# BQ76940.net
KiCad netlist of a schematic drawn in Altium Designer
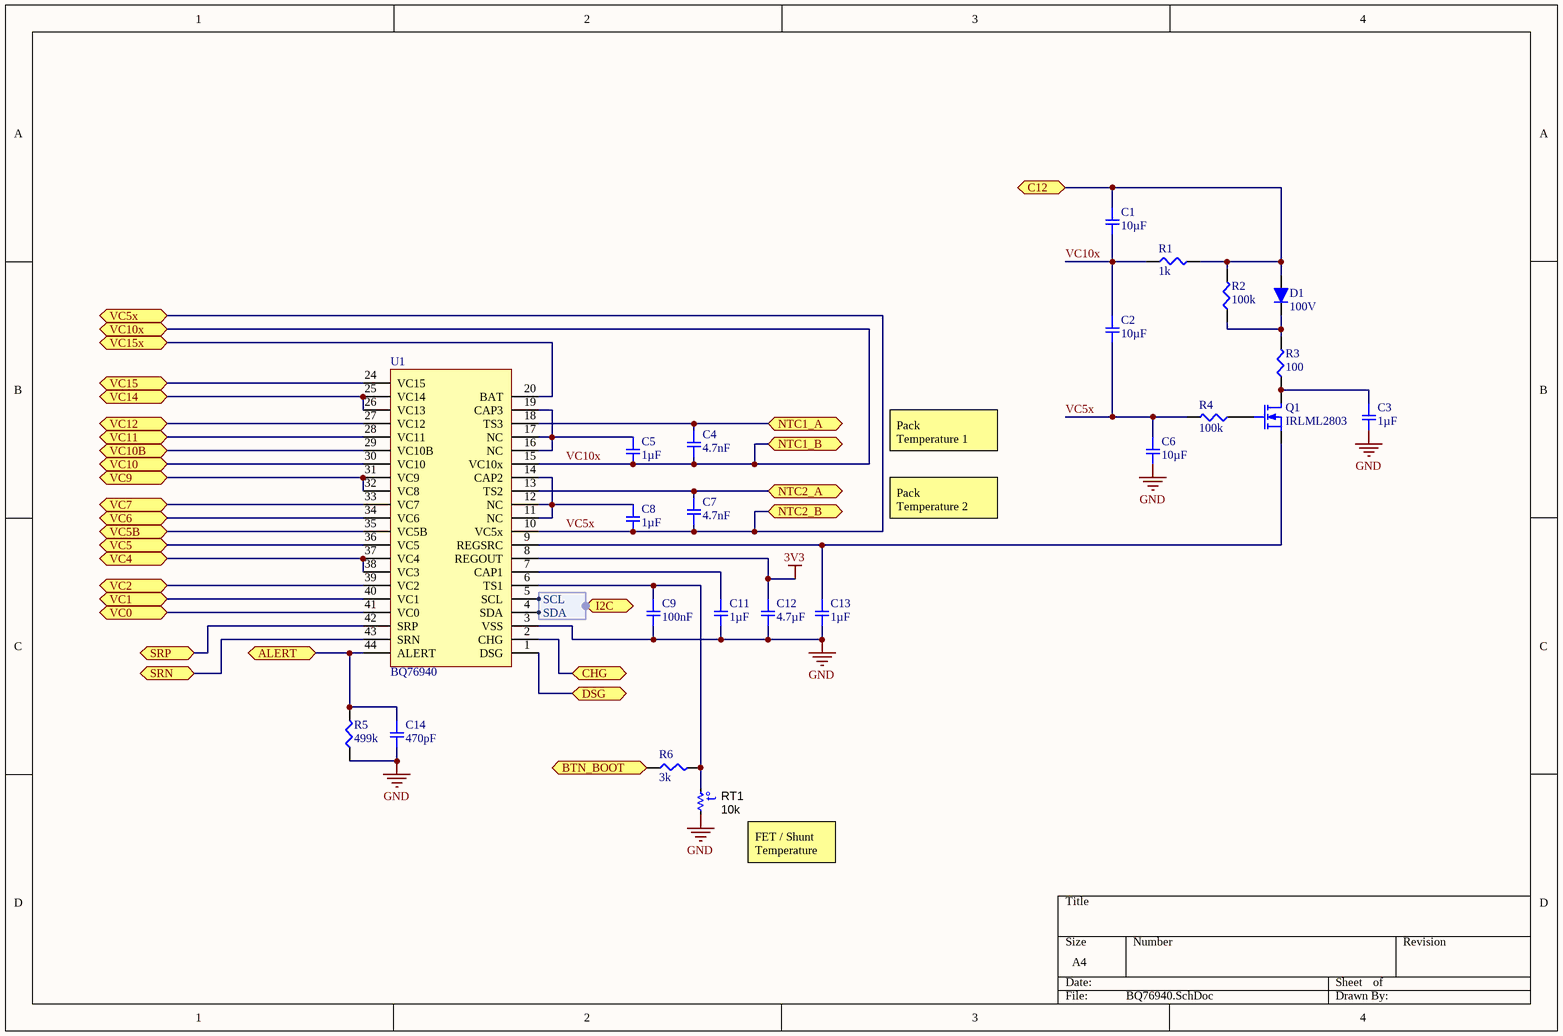
[diagram p0: BQ76940.SchDoc]

(export (version "E")
  (design (tool "Eeschema 10.0.6"))
  (components
    (comp (ref "C1")
      (value "10µF")
      (footprint "SMD-0603C")
      (description "CAP CER 10UF 6.3V X5R 0603")
      (fields
        (field (name "DIGI-KEY PART NUMBER") "490-10467-1-ND")
        (field (name "PART NUMBER") "GRM185R60J106ME15D")
      )
      (libsource (lib "capacitor_murata_0603") (part "GRM185R60J106ME15D"))
    )
    (comp (ref "C2")
      (value "10µF")
      (footprint "SMD-0603C")
      (description "CAP CER 10UF 6.3V X5R 0603")
      (fields
        (field (name "DIGI-KEY PART NUMBER") "490-10467-1-ND")
        (field (name "PART NUMBER") "GRM185R60J106ME15D")
      )
      (libsource (lib "capacitor_murata_0603") (part "GRM185R60J106ME15D"))
    )
    (comp (ref "C3")
      (value "1µF")
      (footprint "SMD-0603C")
      (description "CAP CER 1UF 16V X7R 0603")
      (fields
        (field (name "DIGI-KEY PART NUMBER") "490-5241-1-ND")
        (field (name "PART NUMBER") "GCM188R71C105KA64D")
      )
      (libsource (lib "capacitor_murata_0603") (part "GCM188R71C105KA64D"))
    )
    (comp (ref "C4")
      (value "4.7nF")
      (footprint "SMD-0603C")
      (description "CAP CER 4700PF 50V X7R 0603")
      (fields
        (field (name "DIGI-KEY PART NUMBER") "490-10897-1-ND")
        (field (name "PART NUMBER") "GRJ188R71H472KE11D")
      )
      (libsource (lib "capacitor_murata_0603") (part "GRJ188R71H472KE11D"))
    )
    (comp (ref "C5")
      (value "1µF")
      (footprint "SMD-0603C")
      (description "CAP CER 1UF 16V X7R 0603")
      (fields
        (field (name "DIGI-KEY PART NUMBER") "490-5241-1-ND")
        (field (name "PART NUMBER") "GCM188R71C105KA64D")
      )
      (libsource (lib "capacitor_murata_0603") (part "GCM188R71C105KA64D"))
    )
    (comp (ref "C6")
      (value "10µF")
      (footprint "SMD-0603C")
      (description "CAP CER 10UF 6.3V X5R 0603")
      (fields
        (field (name "DIGI-KEY PART NUMBER") "490-10467-1-ND")
        (field (name "PART NUMBER") "GRM185R60J106ME15D")
      )
      (libsource (lib "capacitor_murata_0603") (part "GRM185R60J106ME15D"))
    )
    (comp (ref "C7")
      (value "4.7nF")
      (footprint "SMD-0603C")
      (description "CAP CER 4700PF 50V X7R 0603")
      (fields
        (field (name "DIGI-KEY PART NUMBER") "490-10897-1-ND")
        (field (name "PART NUMBER") "GRJ188R71H472KE11D")
      )
      (libsource (lib "capacitor_murata_0603") (part "GRJ188R71H472KE11D"))
    )
    (comp (ref "C8")
      (value "1µF")
      (footprint "SMD-0603C")
      (description "CAP CER 1UF 16V X7R 0603")
      (fields
        (field (name "DIGI-KEY PART NUMBER") "490-5241-1-ND")
        (field (name "PART NUMBER") "GCM188R71C105KA64D")
      )
      (libsource (lib "capacitor_murata_0603") (part "GCM188R71C105KA64D"))
    )
    (comp (ref "C9")
      (value "100nF")
      (footprint "SMD-0603C")
      (description "CAP CER 0.1UF 16V X7R 0603")
      (fields
        (field (name "DIGI-KEY PART NUMBER") "490-5796-1-ND")
        (field (name "PART NUMBER") "GCJ188R71C104KA01D")
      )
      (libsource (lib "capacitor_murata_0603") (part "GCJ188R71C104KA01D"))
    )
    (comp (ref "C11")
      (value "1µF")
      (footprint "SMD-0603C")
      (description "CAP CER 1UF 16V X7R 0603")
      (fields
        (field (name "DIGI-KEY PART NUMBER") "490-5241-1-ND")
        (field (name "PART NUMBER") "GCM188R71C105KA64D")
      )
      (libsource (lib "capacitor_murata_0603") (part "GCM188R71C105KA64D"))
    )
    (comp (ref "C12")
      (value "4.7µF")
      (footprint "SMD-0603C")
      (description "CAP CER 4.7UF 6.3V X7S 0603")
      (fields
        (field (name "DIGI-KEY PART NUMBER") "490-10884-1-ND")
        (field (name "PART NUMBER") "GRJ188C70J475KE11D")
      )
      (libsource (lib "capacitor_murata_0603") (part "GRJ188C70J475KE11D"))
    )
    (comp (ref "C13")
      (value "1µF")
      (footprint "SMD-0603C")
      (description "CAP CER 1UF 16V X7R 0603")
      (fields
        (field (name "DIGI-KEY PART NUMBER") "490-5241-1-ND")
        (field (name "PART NUMBER") "GCM188R71C105KA64D")
      )
      (libsource (lib "capacitor_murata_0603") (part "GCM188R71C105KA64D"))
    )
    (comp (ref "C14")
      (value "470pF")
      (footprint "SMD-0603C")
      (description "CAP CER 470PF 50V NP0 0603")
      (fields
        (field (name "DIGI-KEY PART NUMBER") "490-4965-1-ND")
        (field (name "PART NUMBER") "GCM1885C1H471JA16D")
      )
      (libsource (lib "capacitor_murata_0603") (part "GCM1885C1H471JA16D"))
    )
    (comp (ref "D1")
      (value "100V")
      (footprint "SOD-323")
      (description "Diode")
      (libsource (lib "Components") (part "DIODE"))
    )
    (comp (ref "Q1")
      (value "IRLML2803")
      (footprint "SOT23-3")
      (description "N-Channel MOSFET")
      (fields (field (name "PUBLISHER") "Altium Limited"))
      (libsource (lib "Components") (part "MOSFET-N"))
    )
    (comp (ref "R1")
      (value "1k")
      (footprint "SMD-0603-RES")
      (description "RES SMD 1K OHM 1% 1/10W 0603")
      (fields
        (field (name "PART NUMBER") "ERJ-3EKF1001V")
        (field (name "DIGI-KEY PART NUMBER") "P1.00KHCT-ND")
      )
      (libsource (lib "Panasonic_ERJ_0603") (part "ERJ-3EKF1001V"))
    )
    (comp (ref "R2")
      (value "100k")
      (footprint "SMD-0603-RES")
      (description "RES SMD 100K OHM 1% 1/10W 0603")
      (fields
        (field (name "PART NUMBER") "ERJ-3EKF1003V")
        (field (name "DIGI-KEY PART NUMBER") "P100KHCT-ND")
      )
      (libsource (lib "Panasonic_ERJ_0603") (part "ERJ-3EKF1003V"))
    )
    (comp (ref "R3")
      (value "100")
      (footprint "SMD-0603-RES")
      (description "RES SMD 100 OHM 1% 1/10W 0603")
      (fields (field (name "PART NUMBER") "ERJ-3EKF1000V") (field (name "DIGI-KEY PART NUMBER") "P100HCT-ND"))
      (libsource (lib "Panasonic_ERJ_0603") (part "ERJ-3EKF1000V"))
    )
    (comp (ref "R4")
      (value "100k")
      (footprint "SMD-0603-RES")
      (description "RES SMD 100K OHM 1% 1/10W 0603")
      (fields
        (field (name "PART NUMBER") "ERJ-3EKF1003V")
        (field (name "DIGI-KEY PART NUMBER") "P100KHCT-ND")
      )
      (libsource (lib "Panasonic_ERJ_0603") (part "ERJ-3EKF1003V"))
    )
    (comp (ref "R5")
      (value "499k")
      (footprint "SMD-0603-RES")
      (description "RES SMD 499K OHM 1% 1/10W 0603")
      (fields
        (field (name "PART NUMBER") "ERJ-3EKF4993V")
        (field (name "DIGI-KEY PART NUMBER") "P499KHCT-ND")
      )
      (libsource (lib "Panasonic_ERJ_0603") (part "ERJ-3EKF4993V"))
    )
    (comp (ref "R6")
      (value "3k")
      (footprint "SMD-0603-RES")
      (description "RES SMD 3K OHM 1% 1/10W 0603")
      (fields
        (field (name "PART NUMBER") "ERJ-3EKF3001V")
        (field (name "DIGI-KEY PART NUMBER") "P3.00KHCT-ND")
      )
      (libsource (lib "Panasonic_ERJ_0603") (part "ERJ-3EKF3001V"))
    )
    (comp (ref "RT1")
      (value "10k")
      (footprint "SMD-0603-RES")
      (description "Thermistor NTC, 10.0k ohm, 1%")
      (fields
        (field (name "MANUFACTURER") "SEMITEC Corporation")
        (field (name "PARTNUMBER") "103AT-2")
        (field (name "PUBLISHER") "Texas Instruments")
      )
      (libsource (lib "Components") (part "NTC"))
    )
    (comp (ref "U1") (value "BQ76940") (footprint "TSSOP44") (libsource (lib "Components") (part "BQ76940")))
  )
  (nets
    (net (code "2") (name "/ALERT") (class "Default")
      (node (ref "C14") (pin "1") (pinfunction "1_1") (pintype "passive"))
      (node (ref "R5") (pin "2") (pinfunction "2_2") (pintype "passive"))
      (node (ref "U1") (pin "44") (pinfunction "ALERT_44") (pintype "passive"))
    )
    (net (code "3") (name "/BTN_BOOT") (class "Default")
      (node (ref "R6") (pin "1") (pinfunction "1_1") (pintype "passive"))
    )
    (net (code "4") (name "/C12") (class "Default")
      (node (ref "C1") (pin "1") (pinfunction "1_1") (pintype "passive"))
      (node (ref "D1") (pin "2") (pinfunction "A_2") (pintype "passive"))
      (node (ref "R1") (pin "2") (pinfunction "2_2") (pintype "passive"))
      (node (ref "R2") (pin "2") (pinfunction "2_2") (pintype "passive"))
    )
    (net (code "5") (name "/CHG") (class "Default")
      (node (ref "U1") (pin "2") (pinfunction "CHG_2") (pintype "passive"))
    )
    (net (code "6") (name "/DSG") (class "Default")
      (node (ref "U1") (pin "1") (pinfunction "DSG_1") (pintype "passive"))
    )
    (net (code "7") (name "/NTC1_A") (class "Default")
      (node (ref "C4") (pin "1") (pinfunction "1_1") (pintype "passive"))
      (node (ref "U1") (pin "18") (pinfunction "TS3_18") (pintype "passive"))
    )
    (net (code "8") (name "/NTC2_A") (class "Default")
      (node (ref "C7") (pin "1") (pinfunction "1_1") (pintype "passive"))
      (node (ref "U1") (pin "13") (pinfunction "TS2_13") (pintype "passive"))
    )
    (net (code "9") (name "/SCL") (class "Default")
      (node (ref "U1") (pin "5") (pinfunction "SCL_5") (pintype "passive"))
    )
    (net (code "10") (name "/SDA") (class "Default")
      (node (ref "U1") (pin "4") (pinfunction "SDA_4") (pintype "passive"))
    )
    (net (code "11") (name "/SRN") (class "Default")
      (node (ref "U1") (pin "43") (pinfunction "SRN_43") (pintype "passive"))
    )
    (net (code "12") (name "/SRP") (class "Default")
      (node (ref "U1") (pin "42") (pinfunction "SRP_42") (pintype "passive"))
    )
    (net (code "13") (name "/VC0") (class "Default")
      (node (ref "U1") (pin "41") (pinfunction "VC0_41") (pintype "passive"))
    )
    (net (code "14") (name "/VC1") (class "Default")
      (node (ref "U1") (pin "40") (pinfunction "VC1_40") (pintype "passive"))
    )
    (net (code "15") (name "/VC2") (class "Default")
      (node (ref "U1") (pin "39") (pinfunction "VC2_39") (pintype "passive"))
    )
    (net (code "16") (name "/VC4") (class "Default")
      (node (ref "U1") (pin "37") (pinfunction "VC4_37") (pintype "passive"))
      (node (ref "U1") (pin "38") (pinfunction "VC3_38") (pintype "passive"))
    )
    (net (code "17") (name "/VC5") (class "Default")
      (node (ref "U1") (pin "36") (pinfunction "VC5_36") (pintype "passive"))
    )
    (net (code "18") (name "/VC5B") (class "Default")
      (node (ref "U1") (pin "35") (pinfunction "VC5B_35") (pintype "passive"))
    )
    (net (code "19") (name "/VC5x") (class "Default")
      (node (ref "C2") (pin "2") (pinfunction "2_2") (pintype "passive"))
      (node (ref "C6") (pin "1") (pinfunction "1_1") (pintype "passive"))
      (node (ref "C7") (pin "2") (pinfunction "2_2") (pintype "passive"))
      (node (ref "C8") (pin "2") (pinfunction "2_2") (pintype "passive"))
      (node (ref "R4") (pin "2") (pinfunction "2_2") (pintype "passive"))
      (node (ref "U1") (pin "10") (pinfunction "VC5x_10") (pintype "passive"))
    )
    (net (code "20") (name "/VC6") (class "Default")
      (node (ref "U1") (pin "34") (pinfunction "VC6_34") (pintype "passive"))
    )
    (net (code "21") (name "/VC7") (class "Default")
      (node (ref "U1") (pin "33") (pinfunction "VC7_33") (pintype "passive"))
    )
    (net (code "22") (name "/VC9") (class "Default")
      (node (ref "U1") (pin "31") (pinfunction "VC9_31") (pintype "passive"))
      (node (ref "U1") (pin "32") (pinfunction "VC8_32") (pintype "passive"))
    )
    (net (code "23") (name "/VC10") (class "Default")
      (node (ref "U1") (pin "30") (pinfunction "VC10_30") (pintype "passive"))
    )
    (net (code "24") (name "/VC10B") (class "Default")
      (node (ref "U1") (pin "29") (pinfunction "VC10B_29") (pintype "passive"))
    )
    (net (code "25") (name "/VC10x") (class "Default")
      (node (ref "C1") (pin "2") (pinfunction "2_2") (pintype "passive"))
      (node (ref "C2") (pin "1") (pinfunction "1_1") (pintype "passive"))
      (node (ref "C4") (pin "2") (pinfunction "2_2") (pintype "passive"))
      (node (ref "C5") (pin "2") (pinfunction "2_2") (pintype "passive"))
      (node (ref "R1") (pin "1") (pinfunction "1_1") (pintype "passive"))
      (node (ref "U1") (pin "15") (pinfunction "VC10x_15") (pintype "passive"))
    )
    (net (code "26") (name "/VC11") (class "Default")
      (node (ref "U1") (pin "28") (pinfunction "VC11_28") (pintype "passive"))
    )
    (net (code "27") (name "/VC12") (class "Default")
      (node (ref "U1") (pin "27") (pinfunction "VC12_27") (pintype "passive"))
    )
    (net (code "28") (name "/VC14") (class "Default")
      (node (ref "U1") (pin "25") (pinfunction "VC14_25") (pintype "passive"))
      (node (ref "U1") (pin "26") (pinfunction "VC13_26") (pintype "passive"))
    )
    (net (code "29") (name "/VC15") (class "Default")
      (node (ref "U1") (pin "24") (pinfunction "VC15_24") (pintype "passive"))
    )
    (net (code "30") (name "/VC15x") (class "Default")
      (node (ref "U1") (pin "20") (pinfunction "BAT_20") (pintype "passive"))
    )
    (net (code "32") (name "3V3") (class "Default")
      (node (ref "C12") (pin "1") (pinfunction "1_1") (pintype "passive"))
      (node (ref "U1") (pin "8") (pinfunction "REGOUT_8") (pintype "passive"))
    )
    (net (code "33") (name "GND") (class "Default")
      (node (ref "C11") (pin "2") (pinfunction "2_2") (pintype "passive"))
      (node (ref "C12") (pin "2") (pinfunction "2_2") (pintype "passive"))
      (node (ref "C13") (pin "2") (pinfunction "2_2") (pintype "passive"))
      (node (ref "C14") (pin "2") (pinfunction "2_2") (pintype "passive"))
      (node (ref "C3") (pin "2") (pinfunction "2_2") (pintype "passive"))
      (node (ref "C6") (pin "2") (pinfunction "2_2") (pintype "passive"))
      (node (ref "C9") (pin "2") (pinfunction "2_2") (pintype "passive"))
      (node (ref "R5") (pin "1") (pinfunction "1_1") (pintype "passive"))
      (node (ref "RT1") (pin "1") (pinfunction "1_1") (pintype "passive"))
      (node (ref "U1") (pin "3") (pinfunction "VSS_3") (pintype "passive"))
    )
    (net (code "34") (name "Net-(D1-K)") (class "Default")
      (node (ref "D1") (pin "1") (pinfunction "K_1") (pintype "passive"))
      (node (ref "R2") (pin "1") (pinfunction "1_1") (pintype "passive"))
      (node (ref "R3") (pin "2") (pinfunction "2_2") (pintype "passive"))
    )
    (net (code "35") (name "Net-(Q1-D)") (class "Default")
      (node (ref "C3") (pin "1") (pinfunction "1_1") (pintype "passive"))
      (node (ref "Q1") (pin "3") (pinfunction "D_3") (pintype "passive"))
      (node (ref "R3") (pin "1") (pinfunction "1_1") (pintype "passive"))
    )
    (net (code "36") (name "Net-(Q1-G)") (class "Default")
      (node (ref "Q1") (pin "1") (pinfunction "G_1") (pintype "passive"))
      (node (ref "R4") (pin "1") (pinfunction "1_1") (pintype "passive"))
    )
    (net (code "37") (name "Net-(Q1-S)") (class "Default")
      (node (ref "C13") (pin "1") (pinfunction "1_1") (pintype "passive"))
      (node (ref "Q1") (pin "2") (pinfunction "S_2") (pintype "passive"))
      (node (ref "U1") (pin "9") (pinfunction "REGSRC_9") (pintype "passive"))
    )
    (net (code "38") (name "Net-(U1-CAP1)") (class "Default")
      (node (ref "C11") (pin "1") (pinfunction "1_1") (pintype "passive"))
      (node (ref "U1") (pin "7") (pinfunction "CAP1_7") (pintype "passive"))
    )
    (net (code "39") (name "Net-(U1-CAP2)") (class "Default")
      (node (ref "C8") (pin "1") (pinfunction "1_1") (pintype "passive"))
      (node (ref "U1") (pin "11") (pinfunction "NC_11") (pintype "passive"))
      (node (ref "U1") (pin "12") (pinfunction "NC_12") (pintype "passive"))
      (node (ref "U1") (pin "14") (pinfunction "CAP2_14") (pintype "passive"))
    )
    (net (code "40") (name "Net-(U1-CAP3)") (class "Default")
      (node (ref "C5") (pin "1") (pinfunction "1_1") (pintype "passive"))
      (node (ref "U1") (pin "16") (pinfunction "NC_16") (pintype "passive"))
      (node (ref "U1") (pin "17") (pinfunction "NC_17") (pintype "passive"))
      (node (ref "U1") (pin "19") (pinfunction "CAP3_19") (pintype "passive"))
    )
    (net (code "41") (name "Net-(U1-TS1)") (class "Default")
      (node (ref "C9") (pin "1") (pinfunction "1_1") (pintype "passive"))
      (node (ref "R6") (pin "2") (pinfunction "2_2") (pintype "passive"))
      (node (ref "RT1") (pin "2") (pinfunction "2_2") (pintype "passive"))
      (node (ref "U1") (pin "6") (pinfunction "TS1_6") (pintype "passive"))
    )
  )
)
